# buggym2017.net
KiCad netlist of a schematic drawn in EAGLE
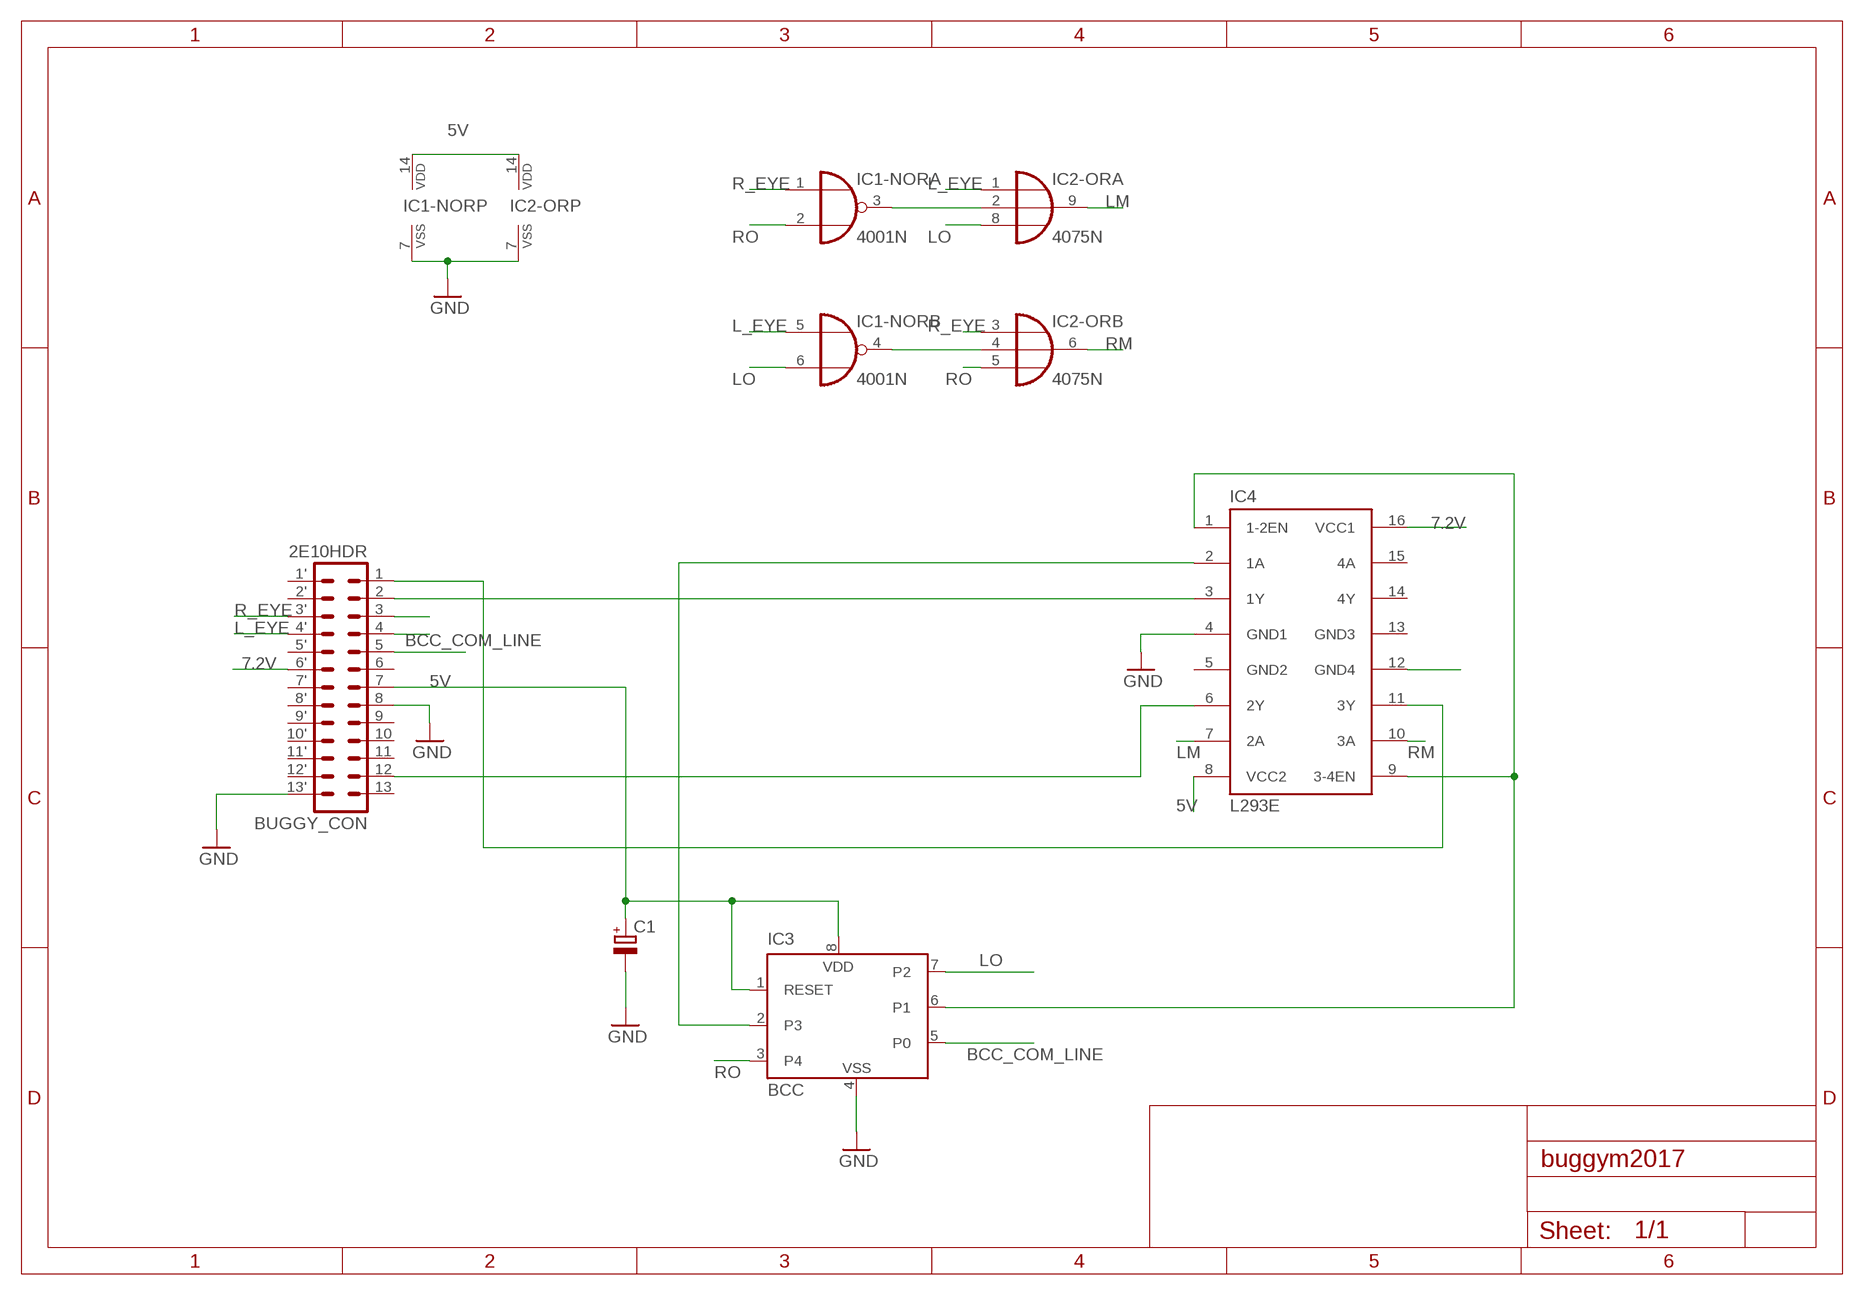
[diagram p0: schematic, sheet 1]

(export (version "E")
  (design (tool "Eeschema 10.0.6"))
  (components
    (comp (ref "BUGGY_CON")
      (value "2E10HDR")
      (footprint "eagle-import:2E10BOARD")
      (libsource (lib "eagle-import") (part "2E10HDR"))
    )
    (comp (ref "C1")
      (value "CPOL-EUE5-4")
      (footprint "eagle-import:E5-4")
      (libsource (lib "eagle-import") (part "CPOL-EUE5-4"))
    )
    (comp (ref "IC1-NOR")
      (value "4001N")
      (footprint "eagle-import:DIL14")
      (libsource (lib "eagle-import") (part "4001N"))
    )
    (comp (ref "IC2-OR")
      (value "4075N")
      (footprint "eagle-import:DIL14")
      (libsource (lib "eagle-import") (part "4075N"))
    )
    (comp (ref "IC3")
      (value "BCC")
      (footprint "eagle-import:DIL8")
      (libsource (lib "eagle-import") (part "BCC"))
    )
    (comp (ref "IC4")
      (value "L293E")
      (footprint "eagle-import:DIL16")
      (fields (field (name "MF") "Arrow Electronics"))
      (libsource (lib "eagle-import") (part "L293E"))
    )
  )
  (nets
    (net (code "1") (name "/5V") (class "Default")
      (node (ref "BUGGY_CON") (pin "7") (pinfunction "7_7") (pintype "passive"))
      (node (ref "C1") (pin "+") (pinfunction "+_+") (pintype "passive"))
      (node (ref "IC1-NOR") (pin "14") (pinfunction "VDD_14") (pintype "power_in"))
      (node (ref "IC2-OR") (pin "14") (pinfunction "VDD_14") (pintype "power_in"))
      (node (ref "IC3") (pin "1") (pinfunction "RESET_1") (pintype "bidirectional"))
      (node (ref "IC3") (pin "8") (pinfunction "5V_8") (pintype "power_in"))
      (node (ref "IC4") (pin "8") (pinfunction "VCC2_8") (pintype "power_in"))
    )
    (net (code "2") (name "/7.2V") (class "Default")
      (node (ref "BUGGY_CON") (pin "6'") (pinfunction "6'_6'") (pintype "passive"))
      (node (ref "IC4") (pin "16") (pinfunction "VCC1_16") (pintype "power_in"))
    )
    (net (code "3") (name "/BCC_COM_LINE") (class "Default")
      (node (ref "BUGGY_CON") (pin "5") (pinfunction "5_5") (pintype "passive"))
      (node (ref "IC3") (pin "5") (pinfunction "P0_5") (pintype "bidirectional"))
    )
    (net (code "4") (name "/GND2") (class "Default")
      (node (ref "IC4") (pin "5") (pinfunction "GND2_5") (pintype "power_in"))
    )
    (net (code "5") (name "/GND3") (class "Default")
      (node (ref "IC4") (pin "13") (pinfunction "GND3_13") (pintype "power_in"))
    )
    (net (code "6") (name "/LM") (class "Default")
      (node (ref "IC2-OR") (pin "9") (pinfunction "O_9") (pintype "output"))
      (node (ref "IC4") (pin "7") (pinfunction "2A_7") (pintype "input"))
    )
    (net (code "7") (name "/LO") (class "Default")
      (node (ref "IC1-NOR") (pin "6") (pinfunction "I1_6") (pintype "input"))
      (node (ref "IC2-OR") (pin "8") (pinfunction "I2_8") (pintype "input"))
      (node (ref "IC3") (pin "7") (pinfunction "P2_7") (pintype "bidirectional"))
    )
    (net (code "8") (name "/L_EYE") (class "Default")
      (node (ref "BUGGY_CON") (pin "4") (pinfunction "4_4") (pintype "passive"))
      (node (ref "BUGGY_CON") (pin "4'") (pinfunction "4'_4'") (pintype "passive"))
      (node (ref "IC1-NOR") (pin "5") (pinfunction "I0_5") (pintype "input"))
      (node (ref "IC2-OR") (pin "1") (pinfunction "I0_1") (pintype "input"))
    )
    (net (code "9") (name "/RM") (class "Default")
      (node (ref "IC2-OR") (pin "6") (pinfunction "O_6") (pintype "output"))
      (node (ref "IC4") (pin "10") (pinfunction "3A_10") (pintype "input"))
    )
    (net (code "10") (name "/RO") (class "Default")
      (node (ref "IC1-NOR") (pin "2") (pinfunction "I1_2") (pintype "input"))
      (node (ref "IC2-OR") (pin "5") (pinfunction "I2_5") (pintype "input"))
      (node (ref "IC3") (pin "3") (pinfunction "P4_3") (pintype "input"))
    )
    (net (code "11") (name "/R_EYE") (class "Default")
      (node (ref "BUGGY_CON") (pin "3") (pinfunction "3_3") (pintype "passive"))
      (node (ref "BUGGY_CON") (pin "3'") (pinfunction "3'_3'") (pintype "passive"))
      (node (ref "IC1-NOR") (pin "1") (pinfunction "I0_1") (pintype "input"))
      (node (ref "IC2-OR") (pin "3") (pinfunction "I0_3") (pintype "input"))
    )
    (net (code "12") (name "GND") (class "Default")
      (node (ref "BUGGY_CON") (pin "13'") (pinfunction "13'_13'") (pintype "passive"))
      (node (ref "BUGGY_CON") (pin "8") (pinfunction "8_8") (pintype "passive"))
      (node (ref "C1") (pin "-") (pinfunction "-_-") (pintype "passive"))
      (node (ref "IC1-NOR") (pin "7") (pinfunction "VSS_7") (pintype "power_in"))
      (node (ref "IC2-OR") (pin "7") (pinfunction "VSS_7") (pintype "power_in"))
      (node (ref "IC3") (pin "4") (pinfunction "VSS_4") (pintype "power_in"))
      (node (ref "IC4") (pin "4") (pinfunction "GND1_4") (pintype "power_in"))
    )
    (net (code "13") (name "Net-(IC1-NORA-O)") (class "Default")
      (node (ref "IC1-NOR") (pin "3") (pinfunction "O_3") (pintype "output"))
      (node (ref "IC2-OR") (pin "2") (pinfunction "I1_2") (pintype "input"))
    )
    (net (code "14") (name "Net-(IC1-NORB-O)") (class "Default")
      (node (ref "IC1-NOR") (pin "4") (pinfunction "O_4") (pintype "output"))
      (node (ref "IC2-OR") (pin "4") (pinfunction "I1_4") (pintype "input"))
    )
    (net (code "15") (name "Net-(IC3-P1)") (class "Default")
      (node (ref "IC3") (pin "6") (pinfunction "P1_6") (pintype "bidirectional"))
      (node (ref "IC4") (pin "1") (pinfunction "1-2EN_1") (pintype "input"))
      (node (ref "IC4") (pin "9") (pinfunction "3-4EN_9") (pintype "input"))
    )
    (net (code "16") (name "Net-(IC3-P3)") (class "Default")
      (node (ref "IC3") (pin "2") (pinfunction "P3_2") (pintype "bidirectional"))
      (node (ref "IC4") (pin "2") (pinfunction "1A_2") (pintype "input"))
    )
    (net (code "17") (name "Net-(IC4-1Y)") (class "Default")
      (node (ref "BUGGY_CON") (pin "2") (pinfunction "2_2") (pintype "passive"))
      (node (ref "IC4") (pin "3") (pinfunction "1Y_3") (pintype "output"))
    )
    (net (code "18") (name "Net-(IC4-2Y)") (class "Default")
      (node (ref "BUGGY_CON") (pin "12") (pinfunction "12_12") (pintype "passive"))
      (node (ref "IC4") (pin "6") (pinfunction "2Y_6") (pintype "output"))
    )
    (net (code "19") (name "Net-(IC4-3Y)") (class "Default")
      (node (ref "BUGGY_CON") (pin "1") (pinfunction "1_1") (pintype "passive"))
      (node (ref "IC4") (pin "11") (pinfunction "3Y_11") (pintype "output"))
    )
    (net (code "20") (name "unconnected-(BUGGY_CON-Pad1')") (class "Default")
      (node (ref "BUGGY_CON") (pin "1'") (pinfunction "1'_1'") (pintype "passive"))
    )
    (net (code "21") (name "unconnected-(BUGGY_CON-Pad2')") (class "Default")
      (node (ref "BUGGY_CON") (pin "2'") (pinfunction "2'_2'") (pintype "passive"))
    )
    (net (code "22") (name "unconnected-(BUGGY_CON-Pad5')") (class "Default")
      (node (ref "BUGGY_CON") (pin "5'") (pinfunction "5'_5'") (pintype "passive"))
    )
    (net (code "23") (name "unconnected-(BUGGY_CON-Pad6)") (class "Default")
      (node (ref "BUGGY_CON") (pin "6") (pinfunction "6_6") (pintype "passive"))
    )
    (net (code "24") (name "unconnected-(BUGGY_CON-Pad7')") (class "Default")
      (node (ref "BUGGY_CON") (pin "7'") (pinfunction "7'_7'") (pintype "passive"))
    )
    (net (code "25") (name "unconnected-(BUGGY_CON-Pad8')") (class "Default")
      (node (ref "BUGGY_CON") (pin "8'") (pinfunction "8'_8'") (pintype "passive"))
    )
    (net (code "26") (name "unconnected-(BUGGY_CON-Pad9')") (class "Default")
      (node (ref "BUGGY_CON") (pin "9'") (pinfunction "9'_9'") (pintype "passive"))
    )
    (net (code "27") (name "unconnected-(BUGGY_CON-Pad9)") (class "Default")
      (node (ref "BUGGY_CON") (pin "9") (pinfunction "9_9") (pintype "passive"))
    )
    (net (code "28") (name "unconnected-(BUGGY_CON-Pad10')") (class "Default")
      (node (ref "BUGGY_CON") (pin "10'") (pinfunction "10'_10'") (pintype "passive"))
    )
    (net (code "29") (name "unconnected-(BUGGY_CON-Pad10)") (class "Default")
      (node (ref "BUGGY_CON") (pin "10") (pinfunction "10_10") (pintype "passive"))
    )
    (net (code "30") (name "unconnected-(BUGGY_CON-Pad11')") (class "Default")
      (node (ref "BUGGY_CON") (pin "11'") (pinfunction "11'_11'") (pintype "passive"))
    )
    (net (code "31") (name "unconnected-(BUGGY_CON-Pad11)") (class "Default")
      (node (ref "BUGGY_CON") (pin "11") (pinfunction "11_11") (pintype "passive"))
    )
    (net (code "32") (name "unconnected-(BUGGY_CON-Pad12')") (class "Default")
      (node (ref "BUGGY_CON") (pin "12'") (pinfunction "12'_12'") (pintype "passive"))
    )
    (net (code "33") (name "unconnected-(BUGGY_CON-Pad13)") (class "Default")
      (node (ref "BUGGY_CON") (pin "13") (pinfunction "13_13") (pintype "passive"))
    )
    (net (code "34") (name "unconnected-(IC4-4A-Pad15)") (class "Default")
      (node (ref "IC4") (pin "15") (pinfunction "4A_15") (pintype "input"))
    )
    (net (code "35") (name "unconnected-(IC4-4Y-Pad14)") (class "Default")
      (node (ref "IC4") (pin "14") (pinfunction "4Y_14") (pintype "output"))
    )
    (net (code "36") (name "unconnected-(IC4-GND4-Pad12)") (class "Default")
      (node (ref "IC4") (pin "12") (pinfunction "GND4_12") (pintype "power_in"))
    )
  )
)
